# Signal_Conditioning.net
KiCad netlist of a schematic drawn in Altium Designer
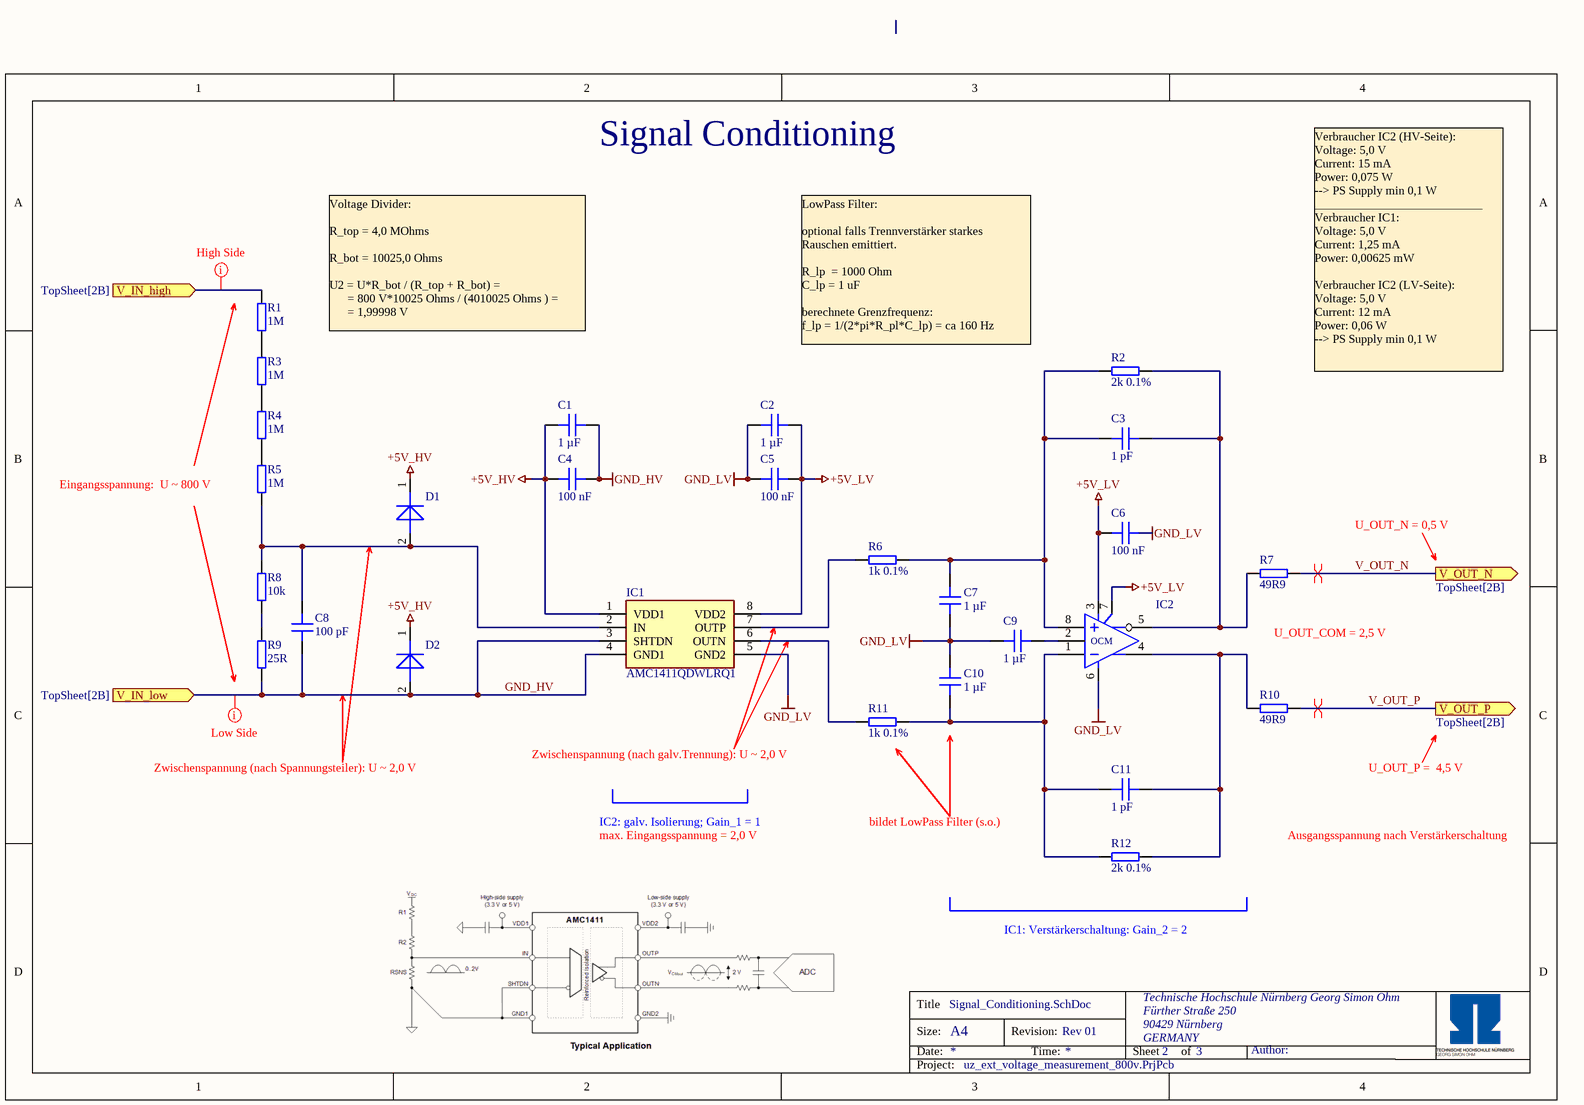
[diagram p0: Signal_Conditioning.SchDoc]

(export (version "E")
  (design (tool "Eeschema 10.0.6"))
  (components
    (comp (ref "C1")
      (value "1 µF")
      (footprint "C_0603")
      (description "50V 1uF X5R ±10% 0603  Multilayer Ceramic Capacitors MLCC - SMD/SMT ROHS")
      (fields
        (field (name "MANUFACTURER") "Samsung Electro-Mechanics")
        (field (name "MANUFACTURER PART NUMBER") "CL10A105KB8NNNC")
        (field (name "CREATED FROM") "MGremer")
      )
      (libsource (lib "user") (part "Capacitor"))
    )
    (comp (ref "C2")
      (value "1 µF")
      (footprint "C_0603")
      (description "50V 1uF X5R ±10% 0603  Multilayer Ceramic Capacitors MLCC - SMD/SMT ROHS")
      (fields
        (field (name "MANUFACTURER") "Samsung Electro-Mechanics")
        (field (name "MANUFACTURER PART NUMBER") "CL10A105KB8NNNC")
        (field (name "CREATED FROM") "MGremer")
      )
      (libsource (lib "user") (part "Capacitor"))
    )
    (comp (ref "C3")
      (value "1 pF")
      (footprint "C_0603")
      (description "Multilayer Ceramic Capacitors MLCC - SMD/SMT 50V 1pF C0G 0603 +/-.1pF")
      (fields
        (field (name "MANUFACTURER PART NUMBER") "KGM15ACG1H1R0BT")
        (field (name "MANUFACTURER") "KYOCERA AVX")
        (field (name "CREATED FROM") "TGaupp")
      )
      (libsource (lib "user") (part "Capacitor"))
    )
    (comp (ref "C4")
      (value "100 nF")
      (footprint "C_0603")
      (description "Capacitor 0603, 6.3 VDC, 100 nF, X5R")
      (fields
        (field (name "MANUFACTURER PART NUMBER") "C0603C104K9PACTU")
        (field (name "MANUFACTURER") "KEMET")
        (field (name "CREATED FROM") "MGremer")
      )
      (libsource (lib "user") (part "Capacitor"))
    )
    (comp (ref "C5")
      (value "100 nF")
      (footprint "C_0603")
      (description "Capacitor 0603, 6.3 VDC, 100 nF, X5R")
      (fields
        (field (name "MANUFACTURER PART NUMBER") "C0603C104K9PACTU")
        (field (name "MANUFACTURER") "KEMET")
        (field (name "CREATED FROM") "MGremer")
      )
      (libsource (lib "user") (part "Capacitor"))
    )
    (comp (ref "C6")
      (value "100 nF")
      (footprint "C_0603")
      (description "Capacitor 0603, 6.3 VDC, 100 nF, X5R")
      (fields
        (field (name "MANUFACTURER PART NUMBER") "C0603C104K9PACTU")
        (field (name "MANUFACTURER") "KEMET")
        (field (name "CREATED FROM") "MGremer")
      )
      (libsource (lib "user") (part "Capacitor"))
    )
    (comp (ref "C7")
      (value "1 µF")
      (footprint "C_0603")
      (description "50V 1uF X5R ±10% 0603  Multilayer Ceramic Capacitors MLCC - SMD/SMT ROHS")
      (fields
        (field (name "MANUFACTURER") "Samsung Electro-Mechanics")
        (field (name "MANUFACTURER PART NUMBER") "CL10A105KB8NNNC")
        (field (name "CREATED FROM") "MGremer")
      )
      (libsource (lib "user") (part "Capacitor"))
    )
    (comp (ref "C8")
      (value "100 pF")
      (footprint "C_0603")
      (description "Capacitor 0603, 50 VDC, 100 pF, C0G")
      (fields
        (field (name "MANUFACTURER PART NUMBER") "885012006057")
        (field (name "MANUFACTURER") "Wuerth Elektronik")
        (field (name "CREATED FROM") "MGremer")
      )
      (libsource (lib "user") (part "Capacitor"))
    )
    (comp (ref "C9")
      (value "1 µF")
      (footprint "C_0603")
      (description "50V 1uF X5R ±10% 0603  Multilayer Ceramic Capacitors MLCC - SMD/SMT ROHS")
      (fields
        (field (name "MANUFACTURER") "Samsung Electro-Mechanics")
        (field (name "MANUFACTURER PART NUMBER") "CL10A105KB8NNNC")
        (field (name "CREATED FROM") "MGremer")
      )
      (libsource (lib "user") (part "Capacitor"))
    )
    (comp (ref "C10")
      (value "1 µF")
      (footprint "C_0603")
      (description "50V 1uF X5R ±10% 0603  Multilayer Ceramic Capacitors MLCC - SMD/SMT ROHS")
      (fields
        (field (name "MANUFACTURER") "Samsung Electro-Mechanics")
        (field (name "MANUFACTURER PART NUMBER") "CL10A105KB8NNNC")
        (field (name "CREATED FROM") "MGremer")
      )
      (libsource (lib "user") (part "Capacitor"))
    )
    (comp (ref "C11")
      (value "1 pF")
      (footprint "C_0603")
      (description "Multilayer Ceramic Capacitors MLCC - SMD/SMT 50V 1pF C0G 0603 +/-.1pF")
      (fields
        (field (name "MANUFACTURER PART NUMBER") "KGM15ACG1H1R0BT")
        (field (name "MANUFACTURER") "KYOCERA AVX")
        (field (name "CREATED FROM") "TGaupp")
      )
      (libsource (lib "user") (part "Capacitor"))
    )
    (comp (ref "D1")
      (value "1SS356VMFHTE-17")
      (footprint "eigene_lib_alt:1SS356VMFHTE17")
      (description "Diode")
      (fields (field (name "MOUSER PART NUMBER") "755-1SS356VMFHTE-17"))
      (libsource (lib "SamacSys") (part "1SS356VMFHTE-17"))
    )
    (comp (ref "D2")
      (value "1SS356VMFHTE-17")
      (footprint "eigene_lib_alt:1SS356VMFHTE17")
      (description "Diode")
      (fields (field (name "MOUSER PART NUMBER") "755-1SS356VMFHTE-17"))
      (libsource (lib "SamacSys") (part "1SS356VMFHTE-17"))
    )
    (comp (ref "IC1")
      (value "AMC1411QDWLRQ1")
      (footprint "SamacSys:SOIC127P1725X403-8N")
      (description "Integrated Circuit")
      (fields (field (name "MOUSER PART NUMBER") "595-AMC1411QDWLRQ1"))
      (libsource (lib "*") (part "AMC1411QDWLRQ1"))
    )
    (comp (ref "IC2")
      (value "ADA4940-1ARZ-R7")
      (footprint "SOIC-8-N")
      (description "Differential ADC Driver")
      (fields (field (name "MANUFACTURER") "Analog Devices") (field (name "CREATED FROM") "MGremer"))
      (libsource (lib "user") (part "ADA4940-1ARZ"))
    )
    (comp (ref "R1")
      (value "1M")
      (footprint "RES 1206_3216")
      (description "SMD resistor 1MOhms .1% 330mW 25PPM/C")
      (fields
        (field (name "MANUFACTURER PART NUMBER") "RS73F2BTTD1004B")
        (field (name "MANUFACTURER") "KOA Speer")
        (field (name "CREATED FROM") "TGaupp")
      )
      (libsource (lib "user") (part "Resistor"))
    )
    (comp (ref "R2")
      (value "2k 0.1%")
      (footprint "RES 1206_3216")
      (description "SMD resistor 2Kohms .1% 400mW 25ppm")
      (fields
        (field (name "MANUFACTURER PART NUMBER") "TNPW12062K00BEEA")
        (field (name "MANUFACTURER") "Vishay")
        (field (name "CREATED FROM") "TGaupp")
      )
      (libsource (lib "user") (part "Resistor"))
    )
    (comp (ref "R3")
      (value "1M")
      (footprint "RES 1206_3216")
      (description "SMD resistor 1MOhms .1% 330mW 25PPM/C")
      (fields
        (field (name "MANUFACTURER PART NUMBER") "RS73F2BTTD1004B")
        (field (name "MANUFACTURER") "KOA Speer")
        (field (name "CREATED FROM") "TGaupp")
      )
      (libsource (lib "user") (part "Resistor"))
    )
    (comp (ref "R4")
      (value "1M")
      (footprint "RES 1206_3216")
      (description "SMD resistor 1MOhms .1% 330mW 25PPM/C")
      (fields
        (field (name "MANUFACTURER PART NUMBER") "RS73F2BTTD1004B")
        (field (name "MANUFACTURER") "KOA Speer")
        (field (name "CREATED FROM") "TGaupp")
      )
      (libsource (lib "user") (part "Resistor"))
    )
    (comp (ref "R5")
      (value "1M")
      (footprint "RES 1206_3216")
      (description "SMD resistor 1MOhms .1% 330mW 25PPM/C")
      (fields
        (field (name "MANUFACTURER PART NUMBER") "RS73F2BTTD1004B")
        (field (name "MANUFACTURER") "KOA Speer")
        (field (name "CREATED FROM") "TGaupp")
      )
      (libsource (lib "user") (part "Resistor"))
    )
    (comp (ref "R6")
      (value "1k 0.1%")
      (footprint "RES 1206_3216")
      (description "SMD resistor 1/4W 1.0Kohm 0.1% 25ppm")
      (fields
        (field (name "MANUFACTURER PART NUMBER") "ERA-8AEB102V")
        (field (name "MANUFACTURER") "Panasonic")
        (field (name "CREATED FROM") "TGaupp")
      )
      (libsource (lib "user") (part "Resistor"))
    )
    (comp (ref "R7")
      (value "49R9")
      (footprint "RES 0603_1608")
      (description "100mW Thick Film Resistors ±100ppm/℃ ±1% 49.9Ω 0603 Chip Resistor - Surface Mount ROHS")
      (fields
        (field (name "MANUFACTURER PART NUMBER") "RC0603FR-0749R9L")
        (field (name "MANUFACTURER") "YAGEO")
        (field (name "CREATED FROM") "AGeiger")
      )
      (libsource (lib "user") (part "Resistor"))
    )
    (comp (ref "R8")
      (value "10k")
      (footprint "RES 1206_3216")
      (description "SMD resistor 10kOhms .1% 330mW 25PPM/C")
      (fields
        (field (name "MANUFACTURER PART NUMBER") "RS73F2BTTD1002B")
        (field (name "MANUFACTURER") "KOA Speer")
        (field (name "CREATED FROM") "TGaupp")
      )
      (libsource (lib "user") (part "Resistor"))
    )
    (comp (ref "R9")
      (value "25R")
      (footprint "RES 0603_1608")
      (description "SMD resistor 0.1%")
      (fields
        (field (name "MANUFACTURER PART NUMBER") "RT0603BRD0725R2L")
        (field (name "MANUFACTURER") "YAGEO")
        (field (name "CREATED FROM") "DHufnagel")
      )
      (libsource (lib "user") (part "Resistor"))
    )
    (comp (ref "R10")
      (value "49R9")
      (footprint "RES 0603_1608")
      (description "100mW Thick Film Resistors ±100ppm/℃ ±1% 49.9Ω 0603 Chip Resistor - Surface Mount ROHS")
      (fields
        (field (name "MANUFACTURER PART NUMBER") "RC0603FR-0749R9L")
        (field (name "MANUFACTURER") "YAGEO")
        (field (name "CREATED FROM") "AGeiger")
      )
      (libsource (lib "user") (part "Resistor"))
    )
    (comp (ref "R11")
      (value "1k 0.1%")
      (footprint "RES 1206_3216")
      (description "SMD resistor 1/4W 1.0Kohm 0.1% 25ppm")
      (fields
        (field (name "MANUFACTURER PART NUMBER") "ERA-8AEB102V")
        (field (name "MANUFACTURER") "Panasonic")
        (field (name "CREATED FROM") "TGaupp")
      )
      (libsource (lib "user") (part "Resistor"))
    )
    (comp (ref "R12")
      (value "2k 0.1%")
      (footprint "RES 1206_3216")
      (description "SMD resistor 2Kohms .1% 400mW 25ppm")
      (fields
        (field (name "MANUFACTURER PART NUMBER") "TNPW12062K00BEEA")
        (field (name "MANUFACTURER") "Vishay")
        (field (name "CREATED FROM") "TGaupp")
      )
      (libsource (lib "user") (part "Resistor"))
    )
  )
  (nets
    (net (code "1") (name "+5V_HV") (class "Default")
      (node (ref "C1") (pin "1") (pinfunction "1_1") (pintype "passive"))
      (node (ref "C4") (pin "1") (pinfunction "1_1") (pintype "passive"))
      (node (ref "D1") (pin "1") (pinfunction "K_1") (pintype "passive"))
      (node (ref "D2") (pin "1") (pinfunction "K_1") (pintype "passive"))
      (node (ref "IC1") (pin "1") (pinfunction "VDD1_1") (pintype "passive"))
    )
    (net (code "2") (name "+5V_LV") (class "Default")
      (node (ref "C2") (pin "2") (pinfunction "2_2") (pintype "passive"))
      (node (ref "C5") (pin "2") (pinfunction "2_2") (pintype "passive"))
      (node (ref "C6") (pin "1") (pinfunction "1_1") (pintype "passive"))
      (node (ref "IC1") (pin "8") (pinfunction "VDD2_8") (pintype "passive"))
      (node (ref "IC2") (pin "3") (pinfunction "V+_3") (pintype "passive"))
      (node (ref "IC2") (pin "7") (pinfunction "EN_7") (pintype "passive"))
    )
    (net (code "3") (name "/V_IN_high") (class "Default")
      (node (ref "R1") (pin "2") (pinfunction "2_2") (pintype "passive"))
    )
    (net (code "4") (name "/V_OUT_N") (class "Default")
      (node (ref "R7") (pin "2") (pinfunction "2_2") (pintype "passive"))
    )
    (net (code "5") (name "/V_OUT_P") (class "Default")
      (node (ref "R10") (pin "2") (pinfunction "2_2") (pintype "passive"))
    )
    (net (code "6") (name "GND_HV") (class "Default")
      (node (ref "C1") (pin "2") (pinfunction "2_2") (pintype "passive"))
      (node (ref "C4") (pin "2") (pinfunction "2_2") (pintype "passive"))
      (node (ref "C8") (pin "1") (pinfunction "1_1") (pintype "passive"))
      (node (ref "D2") (pin "2") (pinfunction "A_2") (pintype "passive"))
      (node (ref "IC1") (pin "3") (pinfunction "SHTDN_3") (pintype "passive"))
      (node (ref "IC1") (pin "4") (pinfunction "GND1_4") (pintype "passive"))
      (node (ref "R9") (pin "1") (pinfunction "1_1") (pintype "passive"))
    )
    (net (code "7") (name "GND_LV") (class "Default")
      (node (ref "C10") (pin "2") (pinfunction "2_2") (pintype "passive"))
      (node (ref "C2") (pin "1") (pinfunction "1_1") (pintype "passive"))
      (node (ref "C5") (pin "1") (pinfunction "1_1") (pintype "passive"))
      (node (ref "C6") (pin "2") (pinfunction "2_2") (pintype "passive"))
      (node (ref "C7") (pin "1") (pinfunction "1_1") (pintype "passive"))
      (node (ref "C9") (pin "1") (pinfunction "1_1") (pintype "passive"))
      (node (ref "IC1") (pin "5") (pinfunction "GND2_5") (pintype "passive"))
      (node (ref "IC2") (pin "6") (pinfunction "V-_6") (pintype "passive"))
    )
    (net (code "8") (name "Net-(C3-Pad2)") (class "Default")
      (node (ref "C3") (pin "2") (pinfunction "2_2") (pintype "passive"))
      (node (ref "IC2") (pin "5") (pinfunction "Out_5") (pintype "passive"))
      (node (ref "R2") (pin "2") (pinfunction "2_2") (pintype "passive"))
      (node (ref "R7") (pin "1") (pinfunction "1_1") (pintype "passive"))
    )
    (net (code "9") (name "Net-(C11-Pad2)") (class "Default")
      (node (ref "C11") (pin "2") (pinfunction "2_2") (pintype "passive"))
      (node (ref "IC2") (pin "4") (pinfunction "Out_4") (pintype "passive"))
      (node (ref "R10") (pin "1") (pinfunction "1_1") (pintype "passive"))
      (node (ref "R12") (pin "2") (pinfunction "2_2") (pintype "passive"))
    )
    (net (code "10") (name "Net-(D1-A)") (class "Default")
      (node (ref "C8") (pin "2") (pinfunction "2_2") (pintype "passive"))
      (node (ref "D1") (pin "2") (pinfunction "A_2") (pintype "passive"))
      (node (ref "IC1") (pin "2") (pinfunction "IN_2") (pintype "passive"))
      (node (ref "R5") (pin "1") (pinfunction "1_1") (pintype "passive"))
      (node (ref "R8") (pin "2") (pinfunction "2_2") (pintype "passive"))
    )
    (net (code "11") (name "Net-(IC1-OUTN)") (class "Default")
      (node (ref "IC1") (pin "6") (pinfunction "OUTN_6") (pintype "passive"))
      (node (ref "R11") (pin "1") (pinfunction "1_1") (pintype "passive"))
    )
    (net (code "12") (name "Net-(IC1-OUTP)") (class "Default")
      (node (ref "IC1") (pin "7") (pinfunction "OUTP_7") (pintype "passive"))
      (node (ref "R6") (pin "1") (pinfunction "1_1") (pintype "passive"))
    )
    (net (code "13") (name "Net-(IC2-+)") (class "Default")
      (node (ref "C3") (pin "1") (pinfunction "1_1") (pintype "passive"))
      (node (ref "C7") (pin "2") (pinfunction "2_2") (pintype "passive"))
      (node (ref "IC2") (pin "8") (pinfunction "+_8") (pintype "passive"))
      (node (ref "R2") (pin "1") (pinfunction "1_1") (pintype "passive"))
      (node (ref "R6") (pin "2") (pinfunction "2_2") (pintype "passive"))
    )
    (net (code "14") (name "Net-(IC2--)") (class "Default")
      (node (ref "C10") (pin "1") (pinfunction "1_1") (pintype "passive"))
      (node (ref "C11") (pin "1") (pinfunction "1_1") (pintype "passive"))
      (node (ref "IC2") (pin "1") (pinfunction "-_1") (pintype "passive"))
      (node (ref "R11") (pin "2") (pinfunction "2_2") (pintype "passive"))
      (node (ref "R12") (pin "1") (pinfunction "1_1") (pintype "passive"))
    )
    (net (code "15") (name "Net-(IC2-OCM)") (class "Default")
      (node (ref "C9") (pin "2") (pinfunction "2_2") (pintype "passive"))
      (node (ref "IC2") (pin "2") (pinfunction "OCM_2") (pintype "passive"))
    )
    (net (code "16") (name "Net-(R1-Pad1)") (class "Default")
      (node (ref "R1") (pin "1") (pinfunction "1_1") (pintype "passive"))
      (node (ref "R3") (pin "2") (pinfunction "2_2") (pintype "passive"))
    )
    (net (code "17") (name "Net-(R3-Pad1)") (class "Default")
      (node (ref "R3") (pin "1") (pinfunction "1_1") (pintype "passive"))
      (node (ref "R4") (pin "2") (pinfunction "2_2") (pintype "passive"))
    )
    (net (code "18") (name "Net-(R4-Pad1)") (class "Default")
      (node (ref "R4") (pin "1") (pinfunction "1_1") (pintype "passive"))
      (node (ref "R5") (pin "2") (pinfunction "2_2") (pintype "passive"))
    )
    (net (code "19") (name "Net-(R8-Pad1)") (class "Default")
      (node (ref "R8") (pin "1") (pinfunction "1_1") (pintype "passive"))
      (node (ref "R9") (pin "2") (pinfunction "2_2") (pintype "passive"))
    )
  )
)
